# TSOC-FTDI-BASE-2-0.net
KiCad netlist of a schematic drawn in EAGLE
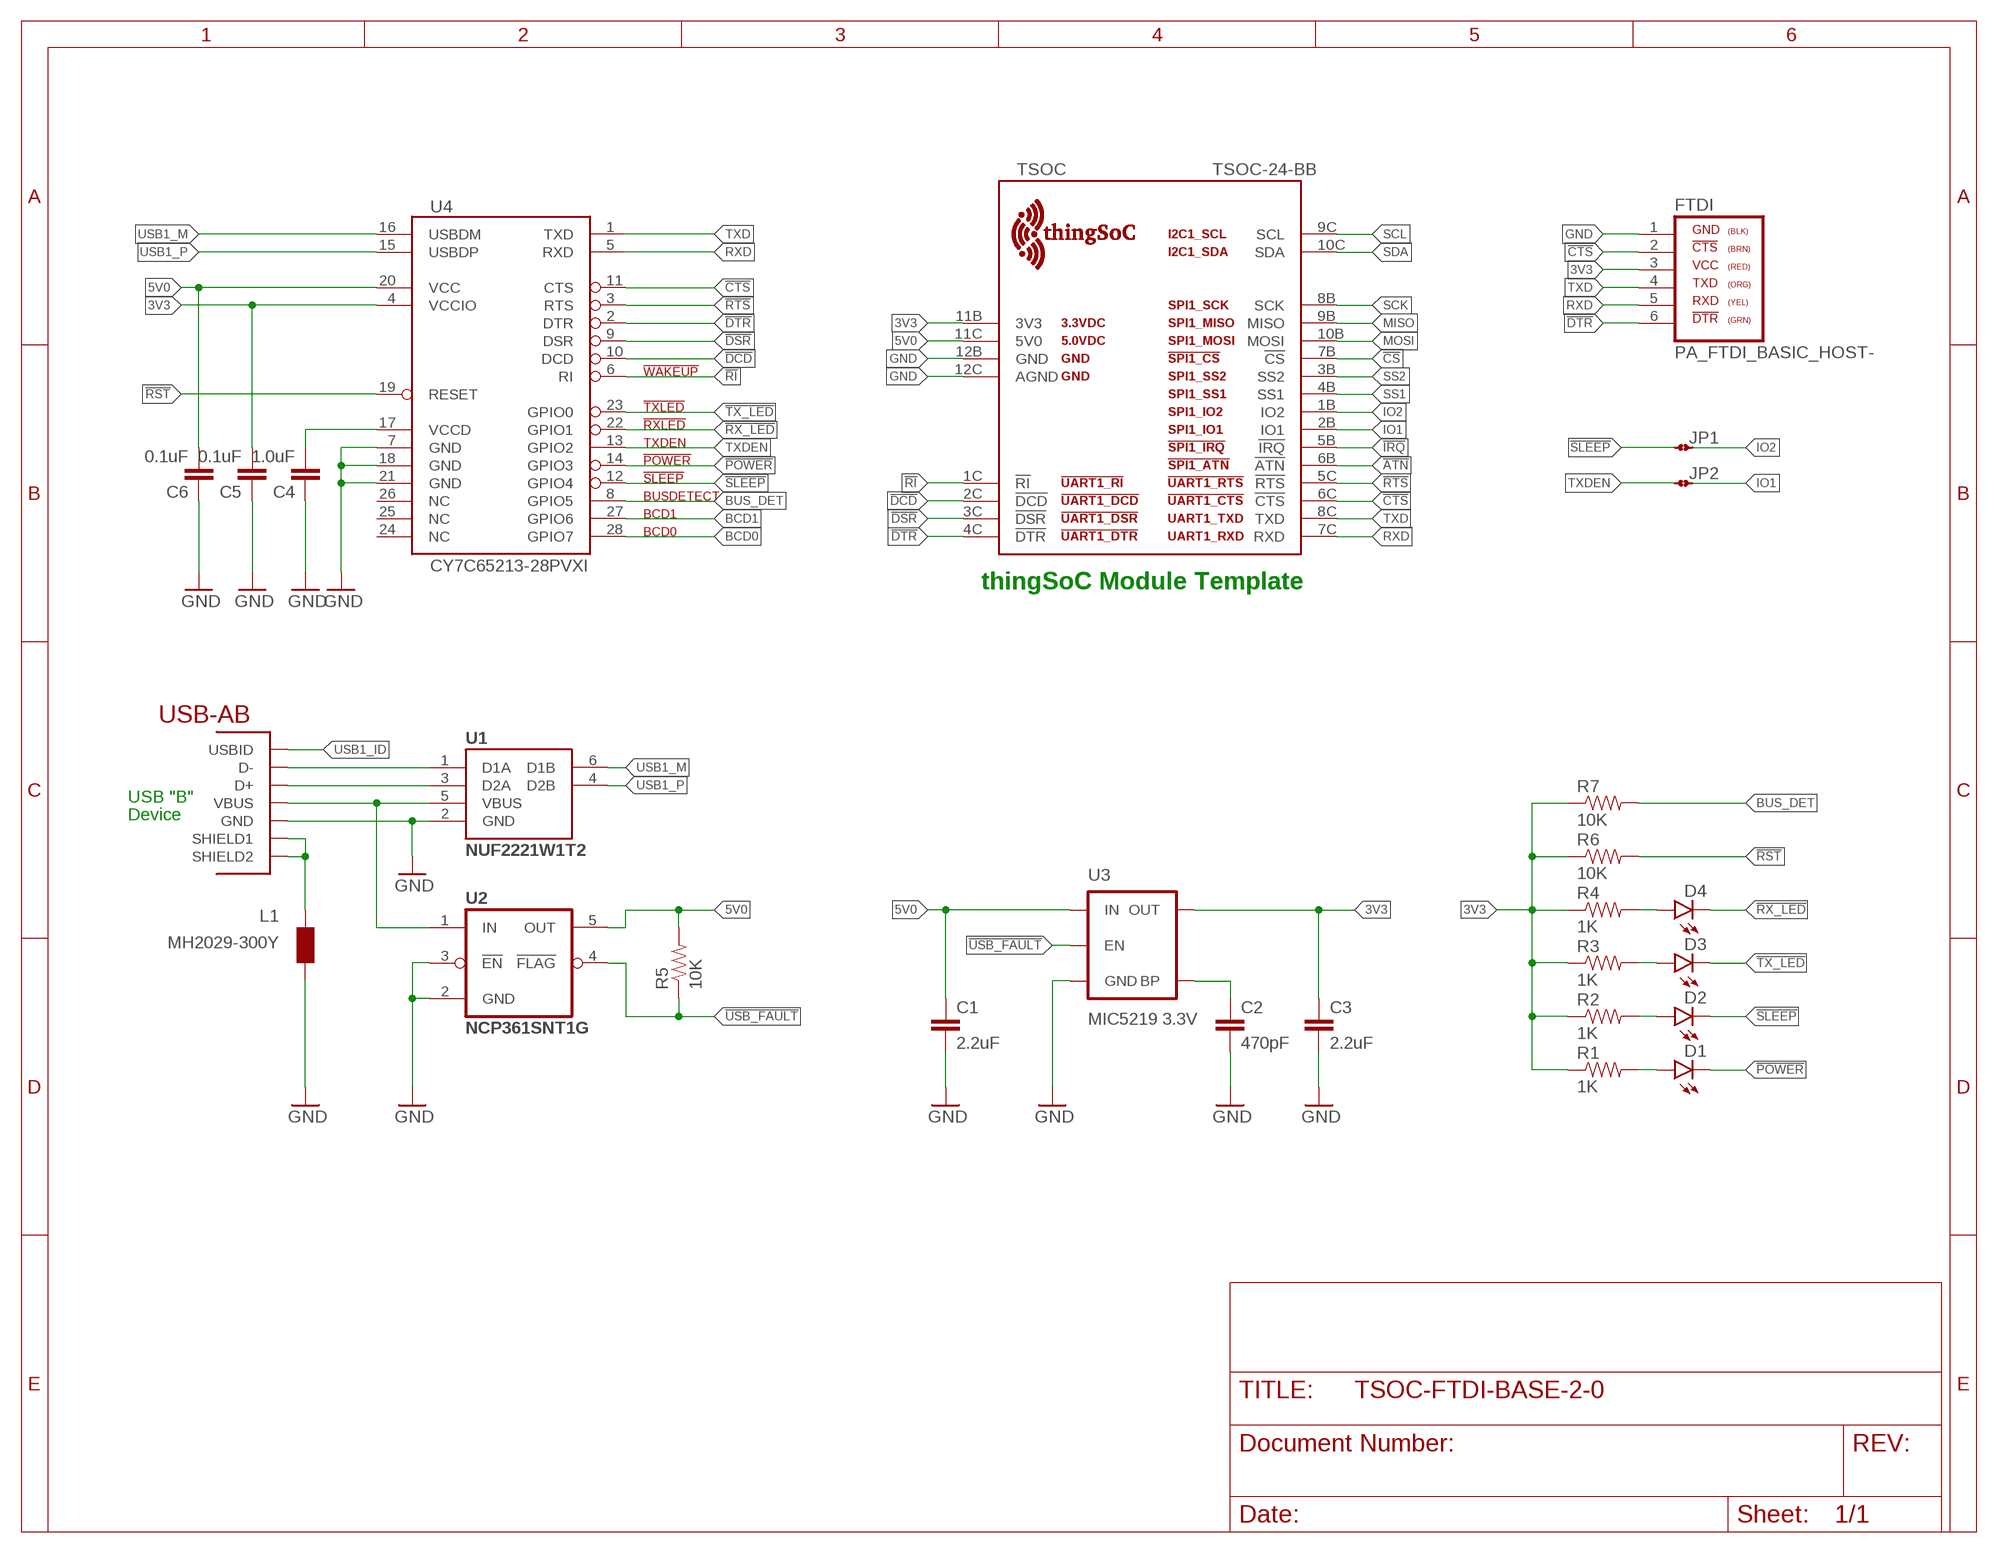
[diagram p0: schematic, sheet 1]

(export (version "E")
  (design (tool "Eeschema 10.0.6"))
  (components
    (comp (ref "C1")
      (value "2.2uF")
      (footprint "eagle-import:0603-CAP")
      (libsource (lib "eagle-import") (part "CAP0603-CAP"))
    )
    (comp (ref "C2")
      (value "470pF")
      (footprint "eagle-import:0603-CAP")
      (libsource (lib "eagle-import") (part "CAP0603-CAP"))
    )
    (comp (ref "C3")
      (value "2.2uF")
      (footprint "eagle-import:0603-CAP")
      (libsource (lib "eagle-import") (part "CAP0603-CAP"))
    )
    (comp (ref "C4")
      (value "1.0uF")
      (footprint "eagle-import:0603-CAP")
      (libsource (lib "eagle-import") (part "CAP0603-CAP"))
    )
    (comp (ref "C5")
      (value "0.1uF")
      (footprint "eagle-import:0603-CAP")
      (libsource (lib "eagle-import") (part "CAP0603-CAP"))
    )
    (comp (ref "C6")
      (value "0.1uF")
      (footprint "eagle-import:0603-CAP")
      (libsource (lib "eagle-import") (part "CAP0603-CAP"))
    )
    (comp (ref "D1")
      (value "LED0603")
      (footprint "eagle-import:LED-0603")
      (libsource (lib "eagle-import") (part "LED0603"))
    )
    (comp (ref "D2")
      (value "LED0603")
      (footprint "eagle-import:LED-0603")
      (libsource (lib "eagle-import") (part "LED0603"))
    )
    (comp (ref "D3")
      (value "LED0603")
      (footprint "eagle-import:LED-0603")
      (libsource (lib "eagle-import") (part "LED0603"))
    )
    (comp (ref "D4")
      (value "LED0603")
      (footprint "eagle-import:LED-0603")
      (libsource (lib "eagle-import") (part "LED0603"))
    )
    (comp (ref "FTDI")
      (value "PA_FTDI_BASIC_HOST-")
      (footprint "eagle-import:PA_FTDI_M5X1")
      (libsource (lib "eagle-import") (part "PA_FTDI_BASIC_HOST-"))
    )
    (comp (ref "JP1")
      (value "JMP-2-NO")
      (footprint "eagle-import:JMP-2-NO")
      (libsource (lib "eagle-import") (part "JMP-2-NO"))
    )
    (comp (ref "JP2")
      (value "JMP-2-NO")
      (footprint "eagle-import:JMP-2-NO")
      (libsource (lib "eagle-import") (part "JMP-2-NO"))
    )
    (comp (ref "L1")
      (value "MH2029-300Y")
      (footprint "eagle-import:0805")
      (libsource (lib "eagle-import") (part "WE-CBF_0805"))
    )
    (comp (ref "R1")
      (value "1K")
      (footprint "eagle-import:0603-RES")
      (libsource (lib "eagle-import") (part "RESISTOR0603-RES"))
    )
    (comp (ref "R2")
      (value "1K")
      (footprint "eagle-import:0603-RES")
      (libsource (lib "eagle-import") (part "RESISTOR0603-RES"))
    )
    (comp (ref "R3")
      (value "1K")
      (footprint "eagle-import:0603-RES")
      (libsource (lib "eagle-import") (part "RESISTOR0603-RES"))
    )
    (comp (ref "R4")
      (value "1K")
      (footprint "eagle-import:0603-RES")
      (libsource (lib "eagle-import") (part "RESISTOR0603-RES"))
    )
    (comp (ref "R5")
      (value "10K")
      (footprint "eagle-import:0603-RES")
      (libsource (lib "eagle-import") (part "RESISTOR0603-RES"))
    )
    (comp (ref "R6")
      (value "10K")
      (footprint "eagle-import:0603-RES")
      (libsource (lib "eagle-import") (part "RESISTOR0603-RES"))
    )
    (comp (ref "R7")
      (value "10K")
      (footprint "eagle-import:0603-RES")
      (libsource (lib "eagle-import") (part "RESISTOR0603-RES"))
    )
    (comp (ref "TSOC")
      (value "TSOC-24-BB")
      (footprint "eagle-import:TSOC-BB-S24")
      (libsource (lib "eagle-import") (part "TSOC-24-BB"))
    )
    (comp (ref "U1")
      (value "NUF2221W1T2")
      (footprint "eagle-import:SOT-363")
      (libsource (lib "eagle-import") (part "NUF2221W1T2"))
    )
    (comp (ref "U2")
      (value "NCP361SNT1G")
      (footprint "eagle-import:SOP95P275X110-5N")
      (libsource (lib "eagle-import") (part "NCP361SNT1G"))
    )
    (comp (ref "U3")
      (value "MIC5219 3.3V")
      (footprint "eagle-import:SOT23-5")
      (libsource (lib "eagle-import") (part "V_REG_MIC52193.3V"))
    )
    (comp (ref "U4")
      (value "CY7C65213-28PVXI")
      (footprint "eagle-import:SSOP28DB")
      (libsource (lib "eagle-import") (part "CY7C65213-28PVXI"))
    )
    (comp (ref "USB1")
      (value "USB_AB")
      (footprint "eagle-import:USB-AB-MICRO-SMD")
      (libsource (lib "eagle-import") (part "USB_AB"))
    )
  )
  (nets
    (net (code "1") (name "/~{ATN}") (class "Default")
      (node (ref "TSOC") (pin "6B") (pinfunction "~{ATN}_6B") (pintype "bidirectional"))
    )
    (net (code "2") (name "/~{CS}") (class "Default")
      (node (ref "TSOC") (pin "7B") (pinfunction "~{CS}_7B") (pintype "bidirectional"))
    )
    (net (code "3") (name "/~{CTS}") (class "Default")
      (node (ref "FTDI") (pin "2") (pinfunction "2_2") (pintype "passive"))
      (node (ref "TSOC") (pin "6C") (pinfunction "~{CTS}_6C") (pintype "bidirectional"))
      (node (ref "U4") (pin "11") (pinfunction "CTS_11") (pintype "input"))
    )
    (net (code "4") (name "/~{DCD}") (class "Default")
      (node (ref "TSOC") (pin "2C") (pinfunction "~{DCD}_2C") (pintype "bidirectional"))
      (node (ref "U4") (pin "10") (pinfunction "DCD_10") (pintype "input"))
    )
    (net (code "5") (name "/~{DSR}") (class "Default")
      (node (ref "TSOC") (pin "3C") (pinfunction "~{DSR}_3C") (pintype "bidirectional"))
      (node (ref "U4") (pin "9") (pinfunction "DSR_9") (pintype "input"))
    )
    (net (code "6") (name "/~{DTR}") (class "Default")
      (node (ref "FTDI") (pin "6") (pinfunction "6_6") (pintype "passive"))
      (node (ref "TSOC") (pin "4C") (pinfunction "~{DTR}_4C") (pintype "bidirectional"))
      (node (ref "U4") (pin "2") (pinfunction "DTR_2") (pintype "output"))
    )
    (net (code "7") (name "/~{IRQ}") (class "Default")
      (node (ref "TSOC") (pin "5B") (pinfunction "~{IRQ}_5B") (pintype "bidirectional"))
    )
    (net (code "8") (name "/~{POWER}") (class "Default")
      (node (ref "D1") (pin "C") (pinfunction "C_C") (pintype "passive"))
      (node (ref "U4") (pin "14") (pinfunction "GPIO3_14") (pintype "output"))
    )
    (net (code "9") (name "/~{RI}") (class "Default")
      (node (ref "TSOC") (pin "1C") (pinfunction "~{RI}_1C") (pintype "bidirectional"))
      (node (ref "U4") (pin "6") (pinfunction "RI_6") (pintype "input"))
    )
    (net (code "10") (name "/~{RST}") (class "Default")
      (node (ref "R6") (pin "2") (pinfunction "2_2") (pintype "passive"))
      (node (ref "U4") (pin "19") (pinfunction "RESET_19") (pintype "input"))
    )
    (net (code "11") (name "/~{RTS}") (class "Default")
      (node (ref "TSOC") (pin "5C") (pinfunction "~{RTS}_5C") (pintype "bidirectional"))
      (node (ref "U4") (pin "3") (pinfunction "RTS_3") (pintype "output"))
    )
    (net (code "12") (name "/~{RX_LED}") (class "Default")
      (node (ref "D4") (pin "C") (pinfunction "C_C") (pintype "passive"))
      (node (ref "U4") (pin "22") (pinfunction "GPIO1_22") (pintype "output"))
    )
    (net (code "13") (name "/~{SLEEP}") (class "Default")
      (node (ref "D2") (pin "C") (pinfunction "C_C") (pintype "passive"))
      (node (ref "JP1") (pin "1") (pinfunction "1_1") (pintype "passive"))
      (node (ref "U4") (pin "12") (pinfunction "GPIO4_12") (pintype "input"))
    )
    (net (code "14") (name "/~{TX_LED}") (class "Default")
      (node (ref "D3") (pin "C") (pinfunction "C_C") (pintype "passive"))
      (node (ref "U4") (pin "23") (pinfunction "GPIO0_23") (pintype "output"))
    )
    (net (code "15") (name "/~{USB_FAULT}") (class "Default")
      (node (ref "R5") (pin "1") (pinfunction "1_1") (pintype "passive"))
      (node (ref "U2") (pin "4") (pinfunction "~{FLAG}_4") (pintype "input"))
      (node (ref "U3") (pin "3") (pinfunction "EN_3") (pintype "input"))
    )
    (net (code "16") (name "3V3") (class "Default")
      (node (ref "C3") (pin "1") (pinfunction "1_1") (pintype "passive"))
      (node (ref "C5") (pin "2") (pinfunction "2_2") (pintype "passive"))
      (node (ref "FTDI") (pin "3") (pinfunction "3_3") (pintype "passive"))
      (node (ref "R1") (pin "1") (pinfunction "1_1") (pintype "passive"))
      (node (ref "R2") (pin "1") (pinfunction "1_1") (pintype "passive"))
      (node (ref "R3") (pin "1") (pinfunction "1_1") (pintype "passive"))
      (node (ref "R4") (pin "1") (pinfunction "1_1") (pintype "passive"))
      (node (ref "R6") (pin "1") (pinfunction "1_1") (pintype "passive"))
      (node (ref "R7") (pin "1") (pinfunction "1_1") (pintype "passive"))
      (node (ref "TSOC") (pin "11B") (pinfunction "3V3_11B") (pintype "bidirectional"))
      (node (ref "U3") (pin "5") (pinfunction "OUT_5") (pintype "passive"))
      (node (ref "U4") (pin "4") (pinfunction "VCCIO_4") (pintype "power_in"))
    )
    (net (code "17") (name "5V0") (class "Default")
      (node (ref "C1") (pin "1") (pinfunction "1_1") (pintype "passive"))
      (node (ref "C6") (pin "2") (pinfunction "2_2") (pintype "passive"))
      (node (ref "R5") (pin "2") (pinfunction "2_2") (pintype "passive"))
      (node (ref "TSOC") (pin "11C") (pinfunction "5V0_11C") (pintype "bidirectional"))
      (node (ref "U2") (pin "5") (pinfunction "OUT_5") (pintype "output"))
      (node (ref "U3") (pin "1") (pinfunction "IN_1") (pintype "input"))
      (node (ref "U4") (pin "20") (pinfunction "VCC_20") (pintype "power_in"))
    )
    (net (code "18") (name "BCD0") (class "Default")
      (node (ref "U4") (pin "28") (pinfunction "GPIO7_28") (pintype "output"))
    )
    (net (code "19") (name "BCD1") (class "Default")
      (node (ref "U4") (pin "27") (pinfunction "GPIO6_27") (pintype "output"))
    )
    (net (code "20") (name "BUS_DET") (class "Default")
      (node (ref "R7") (pin "2") (pinfunction "2_2") (pintype "passive"))
      (node (ref "U4") (pin "8") (pinfunction "GPIO5_8") (pintype "input"))
    )
    (net (code "21") (name "GND") (class "Default")
      (node (ref "C1") (pin "2") (pinfunction "2_2") (pintype "passive"))
      (node (ref "C2") (pin "2") (pinfunction "2_2") (pintype "passive"))
      (node (ref "C3") (pin "2") (pinfunction "2_2") (pintype "passive"))
      (node (ref "C4") (pin "1") (pinfunction "1_1") (pintype "passive"))
      (node (ref "C5") (pin "1") (pinfunction "1_1") (pintype "passive"))
      (node (ref "C6") (pin "1") (pinfunction "1_1") (pintype "passive"))
      (node (ref "FTDI") (pin "1") (pinfunction "1_1") (pintype "passive"))
      (node (ref "L1") (pin "2") (pinfunction "2_2") (pintype "passive"))
      (node (ref "TSOC") (pin "12B") (pinfunction "GND_12B") (pintype "bidirectional"))
      (node (ref "TSOC") (pin "12C") (pinfunction "AGND_12C") (pintype "bidirectional"))
      (node (ref "U1") (pin "2") (pinfunction "GND_2") (pintype "bidirectional"))
      (node (ref "U2") (pin "2") (pinfunction "GND_2") (pintype "passive"))
      (node (ref "U2") (pin "3") (pinfunction "~{EN}_3") (pintype "input"))
      (node (ref "U3") (pin "2") (pinfunction "GND_2") (pintype "input"))
      (node (ref "U4") (pin "18") (pinfunction "GND_18") (pintype "power_in"))
      (node (ref "U4") (pin "21") (pinfunction "GND_21") (pintype "power_in"))
      (node (ref "U4") (pin "7") (pinfunction "GND_7") (pintype "power_in"))
      (node (ref "USB1") (pin "GND") (pinfunction "GND_GND") (pintype "bidirectional"))
    )
    (net (code "22") (name "IO1") (class "Default")
      (node (ref "JP2") (pin "2") (pinfunction "2_2") (pintype "passive"))
      (node (ref "TSOC") (pin "2B") (pinfunction "IO1_2B") (pintype "bidirectional"))
    )
    (net (code "23") (name "IO2") (class "Default")
      (node (ref "JP1") (pin "2") (pinfunction "2_2") (pintype "passive"))
      (node (ref "TSOC") (pin "1B") (pinfunction "IO2_1B") (pintype "bidirectional"))
    )
    (net (code "24") (name "MISO") (class "Default")
      (node (ref "TSOC") (pin "9B") (pinfunction "MISO_9B") (pintype "bidirectional"))
    )
    (net (code "25") (name "MOSI") (class "Default")
      (node (ref "TSOC") (pin "10B") (pinfunction "MOSI_10B") (pintype "bidirectional"))
    )
    (net (code "26") (name "Net-(D1-PadA)") (class "Default")
      (node (ref "D1") (pin "A") (pinfunction "A_A") (pintype "passive"))
      (node (ref "R1") (pin "2") (pinfunction "2_2") (pintype "passive"))
    )
    (net (code "27") (name "Net-(D2-PadA)") (class "Default")
      (node (ref "D2") (pin "A") (pinfunction "A_A") (pintype "passive"))
      (node (ref "R2") (pin "2") (pinfunction "2_2") (pintype "passive"))
    )
    (net (code "28") (name "Net-(D3-PadA)") (class "Default")
      (node (ref "D3") (pin "A") (pinfunction "A_A") (pintype "passive"))
      (node (ref "R3") (pin "2") (pinfunction "2_2") (pintype "passive"))
    )
    (net (code "29") (name "Net-(D4-PadA)") (class "Default")
      (node (ref "D4") (pin "A") (pinfunction "A_A") (pintype "passive"))
      (node (ref "R4") (pin "2") (pinfunction "2_2") (pintype "passive"))
    )
    (net (code "30") (name "Net-(L1-Pad1)") (class "Default")
      (node (ref "L1") (pin "1") (pinfunction "1_1") (pintype "passive"))
      (node (ref "USB1") (pin "SHIELD1") (pinfunction "SHIELD1_SHIELD1") (pintype "bidirectional"))
      (node (ref "USB1") (pin "SHIELD2") (pinfunction "SHIELD2_SHIELD2") (pintype "bidirectional"))
    )
    (net (code "31") (name "Net-(U1-D1A)") (class "Default")
      (node (ref "U1") (pin "1") (pinfunction "D1A_1") (pintype "bidirectional"))
      (node (ref "USB1") (pin "D-") (pinfunction "D-_D-") (pintype "bidirectional"))
    )
    (net (code "32") (name "Net-(U1-D2A)") (class "Default")
      (node (ref "U1") (pin "3") (pinfunction "D2A_3") (pintype "bidirectional"))
      (node (ref "USB1") (pin "D+") (pinfunction "D+_D+") (pintype "bidirectional"))
    )
    (net (code "33") (name "Net-(U1-VBUS)") (class "Default")
      (node (ref "U1") (pin "5") (pinfunction "VBUS_5") (pintype "bidirectional"))
      (node (ref "U2") (pin "1") (pinfunction "IN_1") (pintype "power_in"))
      (node (ref "USB1") (pin "VBUS") (pinfunction "VBUS_VBUS") (pintype "bidirectional"))
    )
    (net (code "34") (name "Net-(U3-BP)") (class "Default")
      (node (ref "C2") (pin "1") (pinfunction "1_1") (pintype "passive"))
      (node (ref "U3") (pin "4") (pinfunction "BP_4") (pintype "input"))
    )
    (net (code "35") (name "Net-(U4-VCCD)") (class "Default")
      (node (ref "C4") (pin "2") (pinfunction "2_2") (pintype "passive"))
      (node (ref "U4") (pin "17") (pinfunction "VCCD_17") (pintype "power_in"))
    )
    (net (code "36") (name "RXD") (class "Default")
      (node (ref "FTDI") (pin "5") (pinfunction "5_5") (pintype "passive"))
      (node (ref "TSOC") (pin "7C") (pinfunction "RXD_7C") (pintype "bidirectional"))
      (node (ref "U4") (pin "5") (pinfunction "RXD_5") (pintype "input"))
    )
    (net (code "37") (name "SCK") (class "Default")
      (node (ref "TSOC") (pin "8B") (pinfunction "SCK_8B") (pintype "bidirectional"))
    )
    (net (code "38") (name "SCL") (class "Default")
      (node (ref "TSOC") (pin "9C") (pinfunction "SCL_9C") (pintype "bidirectional"))
    )
    (net (code "39") (name "SDA") (class "Default")
      (node (ref "TSOC") (pin "10C") (pinfunction "SDA_10C") (pintype "bidirectional"))
    )
    (net (code "40") (name "SS1") (class "Default")
      (node (ref "TSOC") (pin "4B") (pinfunction "SS1_4B") (pintype "bidirectional"))
    )
    (net (code "41") (name "SS2") (class "Default")
      (node (ref "TSOC") (pin "3B") (pinfunction "SS2_3B") (pintype "bidirectional"))
    )
    (net (code "42") (name "TXD") (class "Default")
      (node (ref "FTDI") (pin "4") (pinfunction "4_4") (pintype "passive"))
      (node (ref "TSOC") (pin "8C") (pinfunction "TXD_8C") (pintype "bidirectional"))
      (node (ref "U4") (pin "1") (pinfunction "TXD_1") (pintype "output"))
    )
    (net (code "43") (name "TXDEN") (class "Default")
      (node (ref "JP2") (pin "1") (pinfunction "1_1") (pintype "passive"))
      (node (ref "U4") (pin "13") (pinfunction "GPIO2_13") (pintype "output"))
    )
    (net (code "44") (name "USB1_ID") (class "Default")
      (node (ref "USB1") (pin "ID") (pinfunction "USBID_ID") (pintype "bidirectional"))
    )
    (net (code "45") (name "USB1_M") (class "Default")
      (node (ref "U1") (pin "6") (pinfunction "D1B_6") (pintype "bidirectional"))
      (node (ref "U4") (pin "16") (pinfunction "USBDM_16") (pintype "bidirectional"))
    )
    (net (code "46") (name "USB1_P") (class "Default")
      (node (ref "U1") (pin "4") (pinfunction "D2B_4") (pintype "bidirectional"))
      (node (ref "U4") (pin "15") (pinfunction "USBDP_15") (pintype "bidirectional"))
    )
    (net (code "47") (name "unconnected-(U4-NC-Pad24)") (class "Default")
      (node (ref "U4") (pin "24") (pinfunction "NC_24") (pintype "no_connect"))
    )
    (net (code "48") (name "unconnected-(U4-NC-Pad25)") (class "Default")
      (node (ref "U4") (pin "25") (pinfunction "NC_25") (pintype "no_connect"))
    )
    (net (code "49") (name "unconnected-(U4-NC-Pad26)") (class "Default")
      (node (ref "U4") (pin "26") (pinfunction "NC_26") (pintype "no_connect"))
    )
  )
)
